# etchasketch.net
KiCad netlist of a schematic drawn in EAGLE
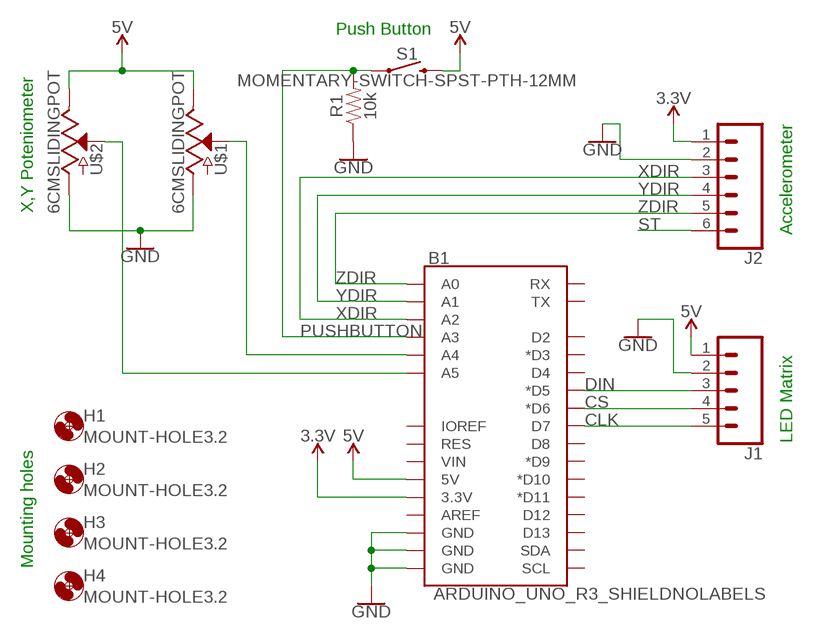
[diagram p0: schematic, sheet 1]

(export (version "E")
  (design (tool "Eeschema 10.0.6"))
  (components
    (comp (ref "B1")
      (value "ARDUINO_UNO_R3_SHIELDNOLABELS")
      (footprint "eagle-import:UNO_R3_SHIELD_NOLABELS")
      (libsource (lib "eagle-import") (part "ARDUINO_UNO_R3_SHIELDNOLABELS"))
    )
    (comp (ref "H1")
      (value "MOUNT-HOLE3.2")
      (footprint "eagle-import:3,2")
      (libsource (lib "eagle-import") (part "MOUNT-HOLE3.2"))
    )
    (comp (ref "H2")
      (value "MOUNT-HOLE3.2")
      (footprint "eagle-import:3,2")
      (libsource (lib "eagle-import") (part "MOUNT-HOLE3.2"))
    )
    (comp (ref "H3")
      (value "MOUNT-HOLE3.2")
      (footprint "eagle-import:3,2")
      (libsource (lib "eagle-import") (part "MOUNT-HOLE3.2"))
    )
    (comp (ref "H4")
      (value "MOUNT-HOLE3.2")
      (footprint "eagle-import:3,2")
      (libsource (lib "eagle-import") (part "MOUNT-HOLE3.2"))
    )
    (comp (ref "J1")
      (value "CONN_05NO_SILK")
      (footprint "eagle-import:1X05_NO_SILK")
      (libsource (lib "eagle-import") (part "CONN_05NO_SILK"))
    )
    (comp (ref "J2")
      (value "CONN_06NO_SILK_NO_POP")
      (footprint "eagle-import:1X06_NO_SILK")
      (libsource (lib "eagle-import") (part "CONN_06NO_SILK_NO_POP"))
    )
    (comp (ref "R1")
      (value "10k")
      (footprint "eagle-import:AXIAL-0.3")
      (libsource (lib "eagle-import") (part "10KOHM-HORIZ-1/4W-5%"))
    )
    (comp (ref "S1")
      (value "MOMENTARY-SWITCH-SPST-PTH-12MM")
      (footprint "eagle-import:TACTILE_SWITCH_PTH_12MM")
      (libsource (lib "eagle-import") (part "MOMENTARY-SWITCH-SPST-PTH-12MM"))
    )
    (comp (ref "U$1")
      (value "6CMSLIDINGPOT")
      (footprint "eagle-import:SLIDINGPOT")
      (libsource (lib "eagle-import") (part "6CMSLIDINGPOT"))
    )
    (comp (ref "U$2")
      (value "6CMSLIDINGPOT")
      (footprint "eagle-import:SLIDINGPOT")
      (libsource (lib "eagle-import") (part "6CMSLIDINGPOT"))
    )
  )
  (nets
    (net (code "1") (name "/CLK") (class "Default")
      (node (ref "B1") (pin "D7") (pinfunction "D7_D7") (pintype "bidirectional"))
      (node (ref "J1") (pin "5") (pinfunction "5_5") (pintype "passive"))
    )
    (net (code "2") (name "/CS") (class "Default")
      (node (ref "B1") (pin "D6") (pinfunction "*D6_D6") (pintype "bidirectional"))
      (node (ref "J1") (pin "4") (pinfunction "4_4") (pintype "passive"))
    )
    (net (code "3") (name "/DIN") (class "Default")
      (node (ref "B1") (pin "D5") (pinfunction "*D5_D5") (pintype "bidirectional"))
      (node (ref "J1") (pin "3") (pinfunction "3_3") (pintype "passive"))
    )
    (net (code "4") (name "/PUSHBUTTON") (class "Default")
      (node (ref "B1") (pin "A3") (pinfunction "A3_A3") (pintype "bidirectional"))
      (node (ref "R1") (pin "P$2") (pinfunction "2_P$2") (pintype "passive"))
      (node (ref "S1") (pin "1") (pinfunction "1_1") (pintype "passive"))
    )
    (net (code "5") (name "/ST") (class "Default")
      (node (ref "J2") (pin "6") (pinfunction "6_6") (pintype "passive"))
    )
    (net (code "6") (name "/XDIR") (class "Default")
      (node (ref "B1") (pin "A2") (pinfunction "A2_A2") (pintype "bidirectional"))
      (node (ref "J2") (pin "3") (pinfunction "3_3") (pintype "passive"))
    )
    (net (code "7") (name "/YDIR") (class "Default")
      (node (ref "B1") (pin "A1") (pinfunction "A1_A1") (pintype "bidirectional"))
      (node (ref "J2") (pin "4") (pinfunction "4_4") (pintype "passive"))
    )
    (net (code "8") (name "/ZDIR") (class "Default")
      (node (ref "B1") (pin "A0") (pinfunction "A0_A0") (pintype "bidirectional"))
      (node (ref "J2") (pin "5") (pinfunction "5_5") (pintype "passive"))
    )
    (net (code "9") (name "3.3V") (class "Default")
      (node (ref "B1") (pin "3.3V") (pinfunction "3.3V_3.3V") (pintype "bidirectional"))
      (node (ref "J2") (pin "1") (pinfunction "1_1") (pintype "passive"))
    )
    (net (code "10") (name "5V") (class "Default")
      (node (ref "B1") (pin "5V") (pinfunction "5V_5V") (pintype "bidirectional"))
      (node (ref "J1") (pin "1") (pinfunction "1_1") (pintype "passive"))
      (node (ref "S1") (pin "3") (pinfunction "2_3") (pintype "passive"))
      (node (ref "U$1") (pin "P$3") (pinfunction "E_P$3") (pintype "passive"))
      (node (ref "U$2") (pin "P$3") (pinfunction "E_P$3") (pintype "passive"))
    )
    (net (code "11") (name "GND") (class "Default")
      (node (ref "B1") (pin "GND@0") (pinfunction "GND_GND@0") (pintype "bidirectional"))
      (node (ref "B1") (pin "GND@1") (pinfunction "GND_GND@1") (pintype "bidirectional"))
      (node (ref "B1") (pin "GND@2") (pinfunction "GND_GND@2") (pintype "bidirectional"))
      (node (ref "J1") (pin "2") (pinfunction "2_2") (pintype "passive"))
      (node (ref "J2") (pin "2") (pinfunction "2_2") (pintype "passive"))
      (node (ref "R1") (pin "P$1") (pinfunction "1_P$1") (pintype "passive"))
      (node (ref "U$1") (pin "P$1") (pinfunction "A_P$1") (pintype "passive"))
      (node (ref "U$2") (pin "P$1") (pinfunction "A_P$1") (pintype "passive"))
    )
    (net (code "12") (name "Net-(U$1-S)") (class "Default")
      (node (ref "B1") (pin "A4") (pinfunction "A4_A4") (pintype "bidirectional"))
      (node (ref "U$1") (pin "P$2") (pinfunction "S_P$2") (pintype "passive"))
    )
    (net (code "13") (name "Net-(U$2-S)") (class "Default")
      (node (ref "B1") (pin "A5") (pinfunction "A5_A5") (pintype "bidirectional"))
      (node (ref "U$2") (pin "P$2") (pinfunction "S_P$2") (pintype "passive"))
    )
    (net (code "14") (name "unconnected-(B1-*D3-PadD3)") (class "Default")
      (node (ref "B1") (pin "D3") (pinfunction "*D3_D3") (pintype "bidirectional"))
    )
    (net (code "15") (name "unconnected-(B1-*D9-PadD9)") (class "Default")
      (node (ref "B1") (pin "D9") (pinfunction "*D9_D9") (pintype "bidirectional"))
    )
    (net (code "16") (name "unconnected-(B1-*D10-PadD10)") (class "Default")
      (node (ref "B1") (pin "D10") (pinfunction "*D10_D10") (pintype "bidirectional"))
    )
    (net (code "17") (name "unconnected-(B1-*D11-PadD11)") (class "Default")
      (node (ref "B1") (pin "D11") (pinfunction "*D11_D11") (pintype "bidirectional"))
    )
    (net (code "18") (name "unconnected-(B1-PadAREF)") (class "Default")
      (node (ref "B1") (pin "AREF") (pinfunction "AREF_AREF") (pintype "bidirectional"))
    )
    (net (code "19") (name "unconnected-(B1-PadD2)") (class "Default")
      (node (ref "B1") (pin "D2") (pinfunction "D2_D2") (pintype "bidirectional"))
    )
    (net (code "20") (name "unconnected-(B1-PadD4)") (class "Default")
      (node (ref "B1") (pin "D4") (pinfunction "D4_D4") (pintype "bidirectional"))
    )
    (net (code "21") (name "unconnected-(B1-PadD8)") (class "Default")
      (node (ref "B1") (pin "D8") (pinfunction "D8_D8") (pintype "bidirectional"))
    )
    (net (code "22") (name "unconnected-(B1-PadD12)") (class "Default")
      (node (ref "B1") (pin "D12") (pinfunction "D12_D12") (pintype "bidirectional"))
    )
    (net (code "23") (name "unconnected-(B1-PadD13)") (class "Default")
      (node (ref "B1") (pin "D13") (pinfunction "D13_D13") (pintype "bidirectional"))
    )
    (net (code "24") (name "unconnected-(B1-PadIOREF)") (class "Default")
      (node (ref "B1") (pin "IOREF") (pinfunction "IOREF_IOREF") (pintype "bidirectional"))
    )
    (net (code "25") (name "unconnected-(B1-PadRES)") (class "Default")
      (node (ref "B1") (pin "RES") (pinfunction "RES_RES") (pintype "bidirectional"))
    )
    (net (code "26") (name "unconnected-(B1-PadRX)") (class "Default")
      (node (ref "B1") (pin "RX") (pinfunction "RX_RX") (pintype "bidirectional"))
    )
    (net (code "27") (name "unconnected-(B1-PadSCL)") (class "Default")
      (node (ref "B1") (pin "SCL") (pinfunction "SCL_SCL") (pintype "bidirectional"))
    )
    (net (code "28") (name "unconnected-(B1-PadSDA)") (class "Default")
      (node (ref "B1") (pin "SDA") (pinfunction "SDA_SDA") (pintype "bidirectional"))
    )
    (net (code "29") (name "unconnected-(B1-PadTX)") (class "Default")
      (node (ref "B1") (pin "TX") (pinfunction "TX_TX") (pintype "bidirectional"))
    )
    (net (code "30") (name "unconnected-(B1-PadVIN)") (class "Default")
      (node (ref "B1") (pin "VIN") (pinfunction "VIN_VIN") (pintype "bidirectional"))
    )
  )
)
